# 5_WIFI.net
KiCad netlist of a schematic drawn in Altium Designer
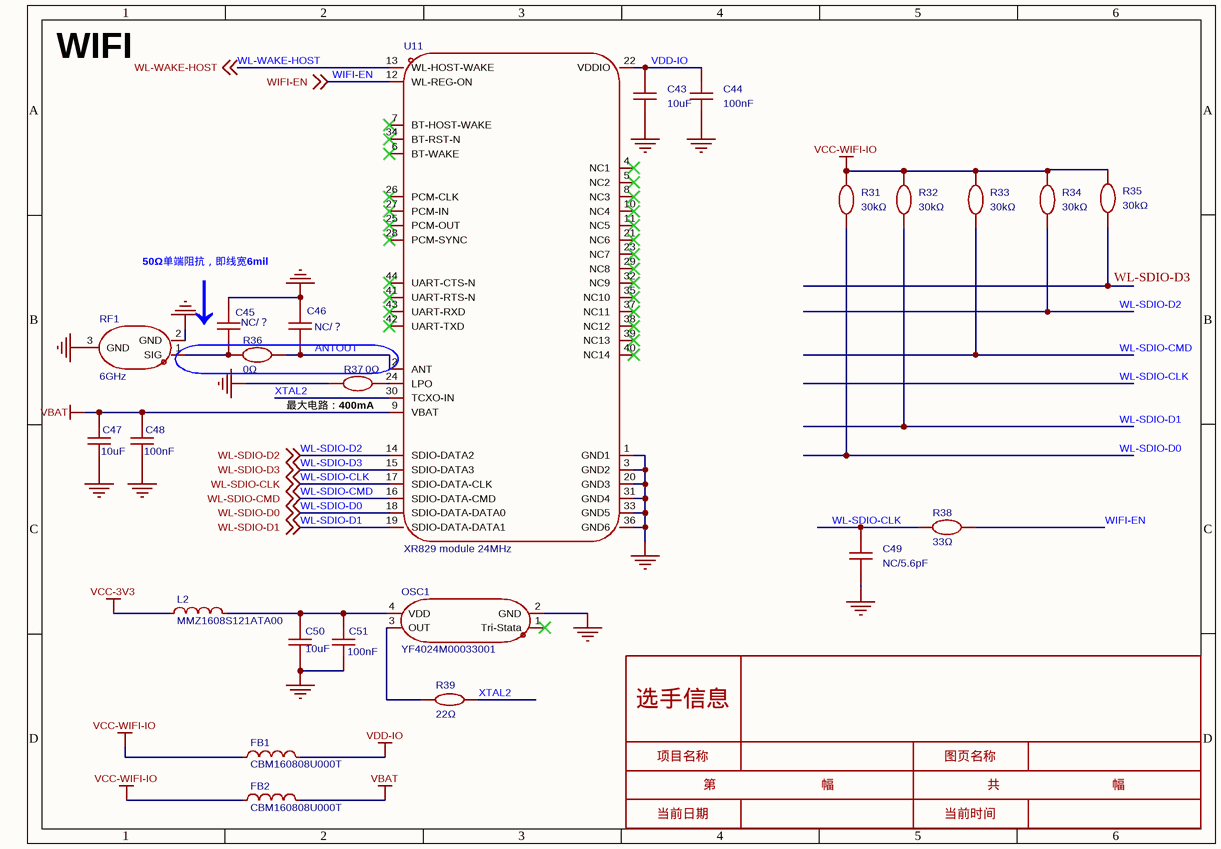
[diagram p0: 5_WIFI.schdoc]

(export (version "E")
  (design (tool "Eeschema 10.0.6"))
  (components
    (comp (ref "C43")
      (value "10uF")
      (footprint "C0805")
      (description "容值:10uF;精度:±10%;额定电压:50V;温度系数:X5R;")
      (fields
        (field (name "MANUFACTURER") "HRE(芯声)")
        (field (name "MANUFACTURER PART") "CGA0805X5R106K500MT")
      )
      (libsource (lib "altium-import") (part "root_1_CGA0805X5R106K500MT_"))
    )
    (comp (ref "C44")
      (value "100nF")
      (footprint "C0402")
      (description "容值:100nF;精度:±10%;额定电压:16V;温度系数:X7R;")
      (fields
        (field (name "MANUFACTURER") "SAMSUNG(三星)")
        (field (name "MANUFACTURER PART") "CL05B104KO5NNNC")
      )
      (libsource (lib "altium-import") (part "root_1_CL05B104KO5NNNC_"))
    )
    (comp (ref "C45")
      (value "NC/？")
      (footprint "C0402")
      (description "容值:100nF;精度:±10%;额定电压:16V;温度系数:X7R;")
      (fields
        (field (name "MANUFACTURER") "SAMSUNG(三星)")
        (field (name "MANUFACTURER PART") "CL05B104KO5NNNC")
      )
      (libsource (lib "altium-import") (part "root_1_CL05B104KO5NNNC_"))
    )
    (comp (ref "C46")
      (value "NC/？")
      (footprint "C0402")
      (description "容值:100nF;精度:±10%;额定电压:16V;温度系数:X7R;")
      (fields
        (field (name "MANUFACTURER") "SAMSUNG(三星)")
        (field (name "MANUFACTURER PART") "CL05B104KO5NNNC")
      )
      (libsource (lib "altium-import") (part "root_1_CL05B104KO5NNNC_"))
    )
    (comp (ref "C47")
      (value "10uF")
      (footprint "C0805")
      (description "容值:10uF;精度:±10%;额定电压:50V;温度系数:X5R;")
      (fields
        (field (name "MANUFACTURER") "HRE(芯声)")
        (field (name "MANUFACTURER PART") "CGA0805X5R106K500MT")
      )
      (libsource (lib "altium-import") (part "root_1_CGA0805X5R106K500MT_"))
    )
    (comp (ref "C48")
      (value "100nF")
      (footprint "C0402")
      (description "容值:100nF;精度:±10%;额定电压:16V;温度系数:X7R;")
      (fields
        (field (name "MANUFACTURER") "SAMSUNG(三星)")
        (field (name "MANUFACTURER PART") "CL05B104KO5NNNC")
      )
      (libsource (lib "altium-import") (part "root_1_CL05B104KO5NNNC_"))
    )
    (comp (ref "C49")
      (value "NC/5.6pF")
      (footprint "C0402")
      (description "容值:100nF;精度:±10%;额定电压:16V;温度系数:X7R;")
      (fields (field (name "MANUFACTURER") "SAMSUNG(三星)") (field (name "MANUFACTURERPART") "CL05B104KO5NNNC"))
      (libsource (lib "altium-import") (part "root_1_mirrored_CL05B104KO5NNNC_"))
    )
    (comp (ref "C50")
      (value "10uF")
      (footprint "C0805")
      (description "容值:10uF;精度:±10%;额定电压:50V;温度系数:X5R;")
      (fields
        (field (name "MANUFACTURER") "HRE(芯声)")
        (field (name "MANUFACTURER PART") "CGA0805X5R106K500MT")
      )
      (libsource (lib "altium-import") (part "root_1_CGA0805X5R106K500MT_"))
    )
    (comp (ref "C51")
      (value "100nF")
      (footprint "C0402")
      (description "容值:100nF;精度:±10%;额定电压:16V;温度系数:X7R;")
      (fields
        (field (name "MANUFACTURER") "SAMSUNG(三星)")
        (field (name "MANUFACTURER PART") "CL05B104KO5NNNC")
      )
      (libsource (lib "altium-import") (part "root_1_CL05B104KO5NNNC_"))
    )
    (comp (ref "FB1")
      (value "CBM160808U000T")
      (footprint "L0603")
      (description "阻抗@频率:0Ω@100MHz;直流电阻(DCR):10mΩ;")
      (fields (field (name "MANUFACTURER") "FH(风华)"))
      (libsource (lib "altium-import") (part "root_0_CBM160808U000T_"))
    )
    (comp (ref "FB2")
      (value "CBM160808U000T")
      (footprint "L0603")
      (description "阻抗@频率:0Ω@100MHz;直流电阻(DCR):10mΩ;")
      (fields (field (name "MANUFACTURER") "FH(风华)"))
      (libsource (lib "altium-import") (part "root_0_CBM160808U000T_"))
    )
    (comp (ref "L2")
      (value "MMZ1608S121ATA00")
      (footprint "L0603")
      (description "阻抗@频率:120Ω@100MHz;误差:±25%;直流电阻(DCR):200mΩ;")
      (fields (field (name "MANUFACTURER") "TDK") (field (name "TOLERANCE") "±25%"))
      (libsource (lib "altium-import") (part "root_0_MMZ1608S121ATA00_"))
    )
    (comp (ref "OSC1")
      (value "YF4024M00033001")
      (footprint "OSC-SMD_4P-L3.2-W2.5-BL_1C210000BB0F")
      (fields (field (name "MANUFACTURER") "HUAXIN(华昕)"))
      (libsource (lib "altium-import") (part "root_2_YF4024M00033001_"))
    )
    (comp (ref "R31")
      (value "30kΩ")
      (footprint "R0402")
      (description "电阻类型:厚膜电阻;阻值:30kΩ;精度:±1%;功率:62.5mW;工作电压:50V;温度系数:±100ppm/℃;")
      (fields (field (name "MANUFACTURER") "FOJAN(富捷)") (field (name "MANUFACTURERPART") "FRC0402F3002TS"))
      (libsource (lib "altium-import") (part "root_1_mirrored_FRC0402F3002TS_"))
    )
    (comp (ref "R32")
      (value "30kΩ")
      (footprint "R0402")
      (description "电阻类型:厚膜电阻;阻值:30kΩ;精度:±1%;功率:62.5mW;工作电压:50V;温度系数:±100ppm/℃;")
      (fields (field (name "MANUFACTURER") "FOJAN(富捷)") (field (name "MANUFACTURERPART") "FRC0402F3002TS"))
      (libsource (lib "altium-import") (part "root_1_mirrored_FRC0402F3002TS_"))
    )
    (comp (ref "R33")
      (value "30kΩ")
      (footprint "R0402")
      (description "电阻类型:厚膜电阻;阻值:30kΩ;精度:±1%;功率:62.5mW;工作电压:50V;温度系数:±100ppm/℃;")
      (fields (field (name "MANUFACTURER") "FOJAN(富捷)") (field (name "MANUFACTURERPART") "FRC0402F3002TS"))
      (libsource (lib "altium-import") (part "root_1_mirrored_FRC0402F3002TS_"))
    )
    (comp (ref "R34")
      (value "30kΩ")
      (footprint "R0402")
      (description "电阻类型:厚膜电阻;阻值:30kΩ;精度:±1%;功率:62.5mW;工作电压:50V;温度系数:±100ppm/℃;")
      (fields (field (name "MANUFACTURER") "FOJAN(富捷)") (field (name "MANUFACTURERPART") "FRC0402F3002TS"))
      (libsource (lib "altium-import") (part "root_1_mirrored_FRC0402F3002TS_"))
    )
    (comp (ref "R35")
      (value "30kΩ")
      (footprint "R0402")
      (description "电阻类型:厚膜电阻;阻值:30kΩ;精度:±1%;功率:62.5mW;工作电压:50V;温度系数:±100ppm/℃;")
      (fields (field (name "MANUFACTURER") "FOJAN(富捷)") (field (name "MANUFACTURERPART") "FRC0402F3002TS"))
      (libsource (lib "altium-import") (part "root_1_mirrored_FRC0402F3002TS_"))
    )
    (comp (ref "R36")
      (value "0Ω")
      (footprint "R0402")
      (description "电阻类型:厚膜电阻;阻值:0Ω;精度:±5%;功率:62.5mW;工作电压:50V;")
      (fields (field (name "MANUFACTURER") "FOJAN(富捷)") (field (name "MANUFACTURER PART") "FRC0402P000 TS"))
      (libsource (lib "altium-import") (part "root_0_FRC0402P000 TS_"))
    )
    (comp (ref "R37")
      (value "0Ω")
      (footprint "R0402")
      (description "电阻类型:厚膜电阻;阻值:0Ω;精度:±5%;功率:62.5mW;工作电压:50V;")
      (fields (field (name "MANUFACTURER") "FOJAN(富捷)") (field (name "MANUFACTURER PART") "FRC0402P000 TS"))
      (libsource (lib "altium-import") (part "root_0_FRC0402P000 TS_"))
    )
    (comp (ref "R38")
      (value "33Ω")
      (footprint "R0402")
      (description "电阻类型:厚膜电阻;阻值:33Ω;精度:±1%;功率:62.5mW;工作电压:50V;温度系数:±100ppm/℃;")
      (fields (field (name "MANUFACTURER") "FOJAN(富捷)") (field (name "MANUFACTURERPART") "FRC0402F33R0TS"))
      (libsource (lib "altium-import") (part "root_0_mirrored_FRC0402F33R0TS_"))
    )
    (comp (ref "R39")
      (value "22Ω")
      (footprint "R0402")
      (description "电阻类型:厚膜电阻;阻值:22Ω;精度:±1%;功率:62.5mW;最大工作电压:50V;温度系数:±100ppm/℃;")
      (fields
        (field (name "MANUFACTURER") "UNI-ROYAL(厚声)")
        (field (name "MANUFACTURERPART") "0402WGF220JTCE")
      )
      (libsource (lib "altium-import") (part "root_2_0402WGF220JTCE_"))
    )
    (comp (ref "RF1")
      (value "6GHz")
      (footprint "IPEX-SMD_BWIPX-1-001E")
      (description "连接器类型:板端;接口类型:内针;端口数量:1;接口直径:2mm;接口长度/高度:1.25mm;频率:6GHz;射频系列:IPEX;阻抗:50Ω;样式:-;工作温度:-40℃~+85℃;")
      (fields
        (field (name "MANUFACTURER") "BAT WIRELESS(蝙蝠无线)")
        (field (name "MANUFACTURER PART") "BWIPX-1-001E")
      )
      (libsource (lib "altium-import") (part "root_2_BWIPX-1-001E_"))
    )
    (comp (ref "U11")
      (value "XR829 module 24MHz")
      (footprint "WIRELM-SMD_XR829-MODULE-24MHZ")
      (fields (field (name "MANUFACTURER") "x-powers"))
      (libsource (lib "altium-import") (part "root_0_XR829 module 24MHz_"))
    )
  )
  (nets
    (net (code "2") (name "/ANTOUT") (class "Default")
      (node (ref "C46") (pin "1") (pinfunction "1_1") (pintype "passive"))
      (node (ref "R36") (pin "2") (pinfunction "2_2") (pintype "passive"))
      (node (ref "U11") (pin "2") (pinfunction "ANT_2") (pintype "passive"))
    )
    (net (code "3") (name "/XTAL2") (class "Default")
      (node (ref "R39") (pin "1") (pinfunction "1_1") (pintype "passive"))
      (node (ref "U11") (pin "30") (pinfunction "TCXO-IN_30") (pintype "passive"))
    )
    (net (code "4") (name "GND") (class "Default")
      (node (ref "C43") (pin "1") (pinfunction "1_1") (pintype "passive"))
      (node (ref "C44") (pin "1") (pinfunction "1_1") (pintype "passive"))
      (node (ref "C45") (pin "2") (pinfunction "2_2") (pintype "passive"))
      (node (ref "C46") (pin "2") (pinfunction "2_2") (pintype "passive"))
      (node (ref "C47") (pin "1") (pinfunction "1_1") (pintype "passive"))
      (node (ref "C48") (pin "1") (pinfunction "1_1") (pintype "passive"))
      (node (ref "C49") (pin "1") (pinfunction "1_1") (pintype "passive"))
      (node (ref "C50") (pin "1") (pinfunction "1_1") (pintype "passive"))
      (node (ref "C51") (pin "1") (pinfunction "1_1") (pintype "passive"))
      (node (ref "OSC1") (pin "2") (pinfunction "GND_2") (pintype "passive"))
      (node (ref "R37") (pin "1") (pinfunction "1_1") (pintype "passive"))
      (node (ref "RF1") (pin "2") (pinfunction "GND_2") (pintype "passive"))
      (node (ref "RF1") (pin "3") (pinfunction "GND_3") (pintype "passive"))
      (node (ref "U11") (pin "1") (pinfunction "GND1_1") (pintype "passive"))
      (node (ref "U11") (pin "20") (pinfunction "GND3_20") (pintype "passive"))
      (node (ref "U11") (pin "3") (pinfunction "GND2_3") (pintype "passive"))
      (node (ref "U11") (pin "31") (pinfunction "GND4_31") (pintype "passive"))
      (node (ref "U11") (pin "33") (pinfunction "GND5_33") (pintype "passive"))
      (node (ref "U11") (pin "36") (pinfunction "GND6_36") (pintype "passive"))
    )
    (net (code "5") (name "Net-(OSC1-OUT)") (class "Default")
      (node (ref "OSC1") (pin "3") (pinfunction "OUT_3") (pintype "passive"))
      (node (ref "R39") (pin "2") (pinfunction "2_2") (pintype "passive"))
    )
    (net (code "6") (name "Net-(OSC1-VDD)") (class "Default")
      (node (ref "C50") (pin "2") (pinfunction "2_2") (pintype "passive"))
      (node (ref "C51") (pin "2") (pinfunction "2_2") (pintype "passive"))
      (node (ref "L2") (pin "2") (pinfunction "2_2") (pintype "passive"))
      (node (ref "OSC1") (pin "4") (pinfunction "VDD_4") (pintype "passive"))
    )
    (net (code "7") (name "Net-(RF1-SIG)") (class "Default")
      (node (ref "C45") (pin "1") (pinfunction "1_1") (pintype "passive"))
      (node (ref "R36") (pin "1") (pinfunction "1_1") (pintype "passive"))
      (node (ref "RF1") (pin "1") (pinfunction "SIG_1") (pintype "passive"))
    )
    (net (code "8") (name "Net-(U11-LPO)") (class "Default")
      (node (ref "R37") (pin "2") (pinfunction "2_2") (pintype "passive"))
      (node (ref "U11") (pin "24") (pinfunction "LPO_24") (pintype "passive"))
    )
    (net (code "9") (name "VBAT") (class "Default")
      (node (ref "C47") (pin "2") (pinfunction "2_2") (pintype "passive"))
      (node (ref "C48") (pin "2") (pinfunction "2_2") (pintype "passive"))
      (node (ref "FB2") (pin "2") (pinfunction "2_2") (pintype "passive"))
      (node (ref "U11") (pin "9") (pinfunction "VBAT_9") (pintype "passive"))
    )
    (net (code "10") (name "VCC-3V3") (class "Default")
      (node (ref "L2") (pin "1") (pinfunction "1_1") (pintype "passive"))
    )
    (net (code "11") (name "VCC-WIFI-IO") (class "Default")
      (node (ref "FB1") (pin "1") (pinfunction "1_1") (pintype "passive"))
      (node (ref "FB2") (pin "1") (pinfunction "1_1") (pintype "passive"))
      (node (ref "R31") (pin "2") (pinfunction "2_2") (pintype "passive"))
      (node (ref "R32") (pin "2") (pinfunction "2_2") (pintype "passive"))
      (node (ref "R33") (pin "2") (pinfunction "2_2") (pintype "passive"))
      (node (ref "R34") (pin "2") (pinfunction "2_2") (pintype "passive"))
      (node (ref "R35") (pin "2") (pinfunction "2_2") (pintype "passive"))
    )
    (net (code "12") (name "VDD-IO") (class "Default")
      (node (ref "C43") (pin "2") (pinfunction "2_2") (pintype "passive"))
      (node (ref "C44") (pin "2") (pinfunction "2_2") (pintype "passive"))
      (node (ref "FB1") (pin "2") (pinfunction "2_2") (pintype "passive"))
      (node (ref "U11") (pin "22") (pinfunction "VDDIO_22") (pintype "passive"))
    )
    (net (code "13") (name "WIFI-EN") (class "Default")
      (node (ref "R38") (pin "1") (pinfunction "1_1") (pintype "passive"))
      (node (ref "U11") (pin "12") (pinfunction "WL-REG-ON_12") (pintype "passive"))
    )
    (net (code "14") (name "WL-SDIO-CLK") (class "Default")
      (node (ref "C49") (pin "2") (pinfunction "2_2") (pintype "passive"))
      (node (ref "R38") (pin "2") (pinfunction "2_2") (pintype "passive"))
      (node (ref "U11") (pin "17") (pinfunction "SDIO-DATA-CLK_17") (pintype "passive"))
    )
    (net (code "15") (name "WL-SDIO-CMD") (class "Default")
      (node (ref "R33") (pin "1") (pinfunction "1_1") (pintype "passive"))
      (node (ref "U11") (pin "16") (pinfunction "SDIO-DATA-CMD_16") (pintype "passive"))
    )
    (net (code "16") (name "WL-SDIO-D0") (class "Default")
      (node (ref "R31") (pin "1") (pinfunction "1_1") (pintype "passive"))
      (node (ref "U11") (pin "18") (pinfunction "SDIO-DATA-DATA0_18") (pintype "passive"))
    )
    (net (code "17") (name "WL-SDIO-D1") (class "Default")
      (node (ref "R32") (pin "1") (pinfunction "1_1") (pintype "passive"))
      (node (ref "U11") (pin "19") (pinfunction "SDIO-DATA-DATA1_19") (pintype "passive"))
    )
    (net (code "18") (name "WL-SDIO-D2") (class "Default")
      (node (ref "R34") (pin "1") (pinfunction "1_1") (pintype "passive"))
      (node (ref "U11") (pin "14") (pinfunction "SDIO-DATA2_14") (pintype "passive"))
    )
    (net (code "19") (name "WL-SDIO-D3") (class "Default")
      (node (ref "R35") (pin "1") (pinfunction "1_1") (pintype "passive"))
      (node (ref "U11") (pin "15") (pinfunction "SDIO-DATA3_15") (pintype "passive"))
    )
    (net (code "20") (name "WL-WAKE-HOST") (class "Default")
      (node (ref "U11") (pin "13") (pinfunction "WL-HOST-WAKE_13") (pintype "passive"))
    )
    (net (code "21") (name "unconnected-(OSC1-Tri-Stata-Pad1)") (class "Default")
      (node (ref "OSC1") (pin "1") (pinfunction "Tri-Stata_1") (pintype "passive+no_connect"))
    )
    (net (code "22") (name "unconnected-(U11-BT-HOST-WAKE-Pad7)") (class "Default")
      (node (ref "U11") (pin "7") (pinfunction "BT-HOST-WAKE_7") (pintype "passive+no_connect"))
    )
    (net (code "23") (name "unconnected-(U11-BT-RST-N-Pad34)") (class "Default")
      (node (ref "U11") (pin "34") (pinfunction "BT-RST-N_34") (pintype "passive+no_connect"))
    )
    (net (code "24") (name "unconnected-(U11-BT-WAKE-Pad6)") (class "Default")
      (node (ref "U11") (pin "6") (pinfunction "BT-WAKE_6") (pintype "passive+no_connect"))
    )
    (net (code "25") (name "unconnected-(U11-NC1-Pad4)") (class "Default")
      (node (ref "U11") (pin "4") (pinfunction "NC1_4") (pintype "passive+no_connect"))
    )
    (net (code "26") (name "unconnected-(U11-NC2-Pad5)") (class "Default")
      (node (ref "U11") (pin "5") (pinfunction "NC2_5") (pintype "passive+no_connect"))
    )
    (net (code "27") (name "unconnected-(U11-NC3-Pad8)") (class "Default")
      (node (ref "U11") (pin "8") (pinfunction "NC3_8") (pintype "passive+no_connect"))
    )
    (net (code "28") (name "unconnected-(U11-NC4-Pad10)") (class "Default")
      (node (ref "U11") (pin "10") (pinfunction "NC4_10") (pintype "passive+no_connect"))
    )
    (net (code "29") (name "unconnected-(U11-NC5-Pad11)") (class "Default")
      (node (ref "U11") (pin "11") (pinfunction "NC5_11") (pintype "passive+no_connect"))
    )
    (net (code "30") (name "unconnected-(U11-NC6-Pad21)") (class "Default")
      (node (ref "U11") (pin "21") (pinfunction "NC6_21") (pintype "passive+no_connect"))
    )
    (net (code "31") (name "unconnected-(U11-NC7-Pad23)") (class "Default")
      (node (ref "U11") (pin "23") (pinfunction "NC7_23") (pintype "passive+no_connect"))
    )
    (net (code "32") (name "unconnected-(U11-NC8-Pad29)") (class "Default")
      (node (ref "U11") (pin "29") (pinfunction "NC8_29") (pintype "passive+no_connect"))
    )
    (net (code "33") (name "unconnected-(U11-NC9-Pad32)") (class "Default")
      (node (ref "U11") (pin "32") (pinfunction "NC9_32") (pintype "passive+no_connect"))
    )
    (net (code "34") (name "unconnected-(U11-NC10-Pad35)") (class "Default")
      (node (ref "U11") (pin "35") (pinfunction "NC10_35") (pintype "passive+no_connect"))
    )
    (net (code "35") (name "unconnected-(U11-NC11-Pad37)") (class "Default")
      (node (ref "U11") (pin "37") (pinfunction "NC11_37") (pintype "passive+no_connect"))
    )
    (net (code "36") (name "unconnected-(U11-NC12-Pad38)") (class "Default")
      (node (ref "U11") (pin "38") (pinfunction "NC12_38") (pintype "passive+no_connect"))
    )
    (net (code "37") (name "unconnected-(U11-NC13-Pad39)") (class "Default")
      (node (ref "U11") (pin "39") (pinfunction "NC13_39") (pintype "passive+no_connect"))
    )
    (net (code "38") (name "unconnected-(U11-NC14-Pad40)") (class "Default")
      (node (ref "U11") (pin "40") (pinfunction "NC14_40") (pintype "passive+no_connect"))
    )
    (net (code "39") (name "unconnected-(U11-PCM-CLK-Pad26)") (class "Default")
      (node (ref "U11") (pin "26") (pinfunction "PCM-CLK_26") (pintype "passive+no_connect"))
    )
    (net (code "40") (name "unconnected-(U11-PCM-IN-Pad27)") (class "Default")
      (node (ref "U11") (pin "27") (pinfunction "PCM-IN_27") (pintype "passive+no_connect"))
    )
    (net (code "41") (name "unconnected-(U11-PCM-OUT-Pad25)") (class "Default")
      (node (ref "U11") (pin "25") (pinfunction "PCM-OUT_25") (pintype "passive+no_connect"))
    )
    (net (code "42") (name "unconnected-(U11-PCM-SYNC-Pad28)") (class "Default")
      (node (ref "U11") (pin "28") (pinfunction "PCM-SYNC_28") (pintype "passive+no_connect"))
    )
    (net (code "43") (name "unconnected-(U11-UART-CTS-N-Pad44)") (class "Default")
      (node (ref "U11") (pin "44") (pinfunction "UART-CTS-N_44") (pintype "passive+no_connect"))
    )
    (net (code "44") (name "unconnected-(U11-UART-RTS-N-Pad41)") (class "Default")
      (node (ref "U11") (pin "41") (pinfunction "UART-RTS-N_41") (pintype "passive+no_connect"))
    )
    (net (code "45") (name "unconnected-(U11-UART-RXD-Pad43)") (class "Default")
      (node (ref "U11") (pin "43") (pinfunction "UART-RXD_43") (pintype "passive+no_connect"))
    )
    (net (code "46") (name "unconnected-(U11-UART-TXD-Pad42)") (class "Default")
      (node (ref "U11") (pin "42") (pinfunction "UART-TXD_42") (pintype "passive+no_connect"))
    )
  )
)
